# 5V_buck.net
KiCad netlist of a schematic drawn in Altium Designer
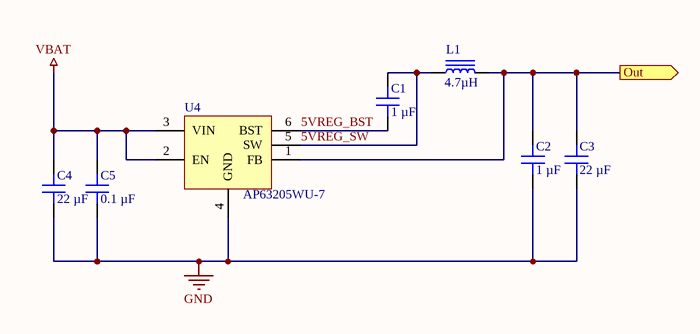
[diagram p0: 5V_buck.SchDoc]

(export (version "E")
  (design (tool "Eeschema 10.0.6"))
  (components
    (comp (ref "C1")
      (value "1 µF")
      (footprint "CAP 0402_1005")
      (description "CAP CER 0.1UF 16V X7R 0402")
      (fields (field (name "PART NUMBER") "C0402C104K4RACAUTO") (field (name "MANUFACTURER") "KEMET"))
      (libsource (lib "Celestial Altium Library - altium_library") (part "Capacitor"))
    )
    (comp (ref "C2")
      (value "1 µF")
      (footprint "CAP 0402_1005")
      (description "CAP CER 0.1UF 16V X7R 0402")
      (fields (field (name "PART NUMBER") "C0402C104K4RACAUTO") (field (name "MANUFACTURER") "KEMET"))
      (libsource (lib "Celestial Altium Library - altium_library") (part "Capacitor"))
    )
    (comp (ref "C3")
      (value "22 µF")
      (footprint "CAP 0402_1005")
      (description "CAP CER 0.1UF 16V X7R 0402")
      (fields (field (name "PART NUMBER") "C0402C104K4RACAUTO") (field (name "MANUFACTURER") "KEMET"))
      (libsource (lib "Celestial Altium Library - altium_library") (part "Capacitor"))
    )
    (comp (ref "C4")
      (value "22 µF")
      (footprint "CAP 0603_1608")
      (description "CAP CER 47UF 6.3V X5R 0603")
      (fields
        (field (name "PART NUMBER") "C0603B476M007T")
        (field (name "MANUFACTURER") "Holy Stone Enterprise Co., Ltd.")
      )
      (libsource (lib "Celestial Altium Library - altium_library") (part "Capacitor"))
    )
    (comp (ref "C5")
      (value "0.1 µF")
      (footprint "CAP 0402_1005")
      (description "CAP CER 0.1UF 16V X7R 0402")
      (fields (field (name "PART NUMBER") "C0402C104K4RACAUTO") (field (name "MANUFACTURER") "KEMET"))
      (libsource (lib "Celestial Altium Library - altium_library") (part "Capacitor"))
    )
    (comp (ref "L1")
      (value "4.7µH")
      (footprint "IND 1008_2520")
      (description "FIXED IND 4.7UH 1A 110 MOHM SMD")
      (fields (field (name "PART NUMBER") "MLP2520S4R7ST0S1") (field (name "MANUFACTURER") "TDK Corporation"))
      (libsource (lib "Celestial Altium Library - altium_library") (part "Inductor"))
    )
    (comp (ref "U4")
      (value "AP63205WU-7")
      (footprint "TSOT-26-6 - 3.2mm")
      (description "5V fixed step down Buck")
      (libsource (lib "IC") (part "AP63205WU-7"))
    )
  )
  (nets
    (net (code "1") (name "/5VREG_BST") (class "Default")
      (node (ref "C1") (pin "1") (pinfunction "1_1") (pintype "passive"))
      (node (ref "U4") (pin "6") (pinfunction "BST_6") (pintype "passive"))
    )
    (net (code "2") (name "/5VREG_SW") (class "Default")
      (node (ref "C1") (pin "2") (pinfunction "2_2") (pintype "passive"))
      (node (ref "L1") (pin "1") (pinfunction "1_1") (pintype "passive"))
      (node (ref "U4") (pin "5") (pinfunction "SW_5") (pintype "passive"))
    )
    (net (code "3") (name "/Out") (class "Default")
      (node (ref "C2") (pin "2") (pinfunction "2_2") (pintype "passive"))
      (node (ref "C3") (pin "2") (pinfunction "2_2") (pintype "passive"))
      (node (ref "L1") (pin "2") (pinfunction "2_2") (pintype "passive"))
      (node (ref "U4") (pin "1") (pinfunction "FB_1") (pintype "passive"))
    )
    (net (code "4") (name "GND") (class "Default")
      (node (ref "C2") (pin "1") (pinfunction "1_1") (pintype "passive"))
      (node (ref "C3") (pin "1") (pinfunction "1_1") (pintype "passive"))
      (node (ref "C4") (pin "1") (pinfunction "1_1") (pintype "passive"))
      (node (ref "C5") (pin "1") (pinfunction "1_1") (pintype "passive"))
      (node (ref "U4") (pin "4") (pinfunction "GND_4") (pintype "passive"))
    )
    (net (code "5") (name "VBAT") (class "Default")
      (node (ref "C4") (pin "2") (pinfunction "2_2") (pintype "passive"))
      (node (ref "C5") (pin "2") (pinfunction "2_2") (pintype "passive"))
      (node (ref "U4") (pin "2") (pinfunction "EN_2") (pintype "passive"))
      (node (ref "U4") (pin "3") (pinfunction "VIN_3") (pintype "passive"))
    )
  )
)
